# SPINE_CONNECTOR.net
KiCad netlist of a schematic drawn in Altium Designer
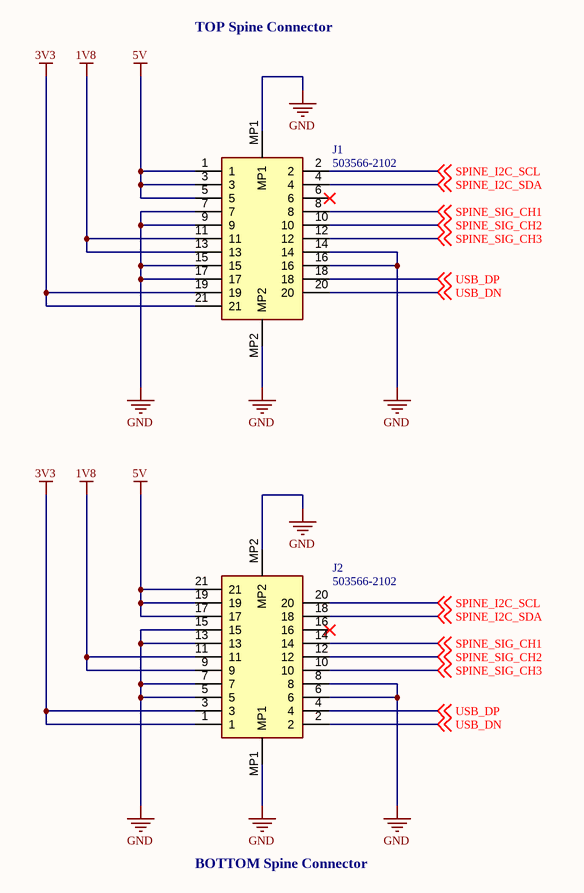
[diagram p0: SPINE_CONNECTOR.SchDoc]

(export (version "E")
  (design (tool "Eeschema 10.0.6"))
  (components
    (comp (ref "J1")
      (value "503566-2102")
      (footprint "SamacSys:5035662102")
      (description "Connector")
      (fields (field (name "MOUSER PART NUMBER") "538-503566-2102"))
      (libsource (lib "*") (part "503566-2102"))
    )
    (comp (ref "J2")
      (value "503566-2102")
      (footprint "SamacSys:5035662102")
      (description "Connector")
      (fields (field (name "MOUSER PART NUMBER") "538-503566-2102"))
      (libsource (lib "") (part "503566-2102_1"))
    )
  )
  (nets
    (net (code "1") (name "1V8") (class "Default")
      (node (ref "J1") (pin "11") (pinfunction "11_11") (pintype "passive"))
      (node (ref "J1") (pin "13") (pinfunction "13_13") (pintype "passive"))
      (node (ref "J2") (pin "11") (pinfunction "11_11") (pintype "passive"))
      (node (ref "J2") (pin "9") (pinfunction "9_9") (pintype "passive"))
    )
    (net (code "2") (name "3V3") (class "Default")
      (node (ref "J1") (pin "19") (pinfunction "19_19") (pintype "passive"))
      (node (ref "J1") (pin "21") (pinfunction "21_21") (pintype "passive"))
      (node (ref "J2") (pin "1") (pinfunction "1_1") (pintype "passive"))
      (node (ref "J2") (pin "3") (pinfunction "3_3") (pintype "passive"))
    )
    (net (code "3") (name "5V") (class "Default")
      (node (ref "J1") (pin "1") (pinfunction "1_1") (pintype "passive"))
      (node (ref "J1") (pin "3") (pinfunction "3_3") (pintype "passive"))
      (node (ref "J1") (pin "5") (pinfunction "5_5") (pintype "passive"))
      (node (ref "J2") (pin "17") (pinfunction "17_17") (pintype "passive"))
      (node (ref "J2") (pin "19") (pinfunction "19_19") (pintype "passive"))
      (node (ref "J2") (pin "21") (pinfunction "21_21") (pintype "passive"))
    )
    (net (code "4") (name "GND") (class "Default")
      (node (ref "J1") (pin "14") (pinfunction "14_14") (pintype "passive"))
      (node (ref "J1") (pin "15") (pinfunction "15_15") (pintype "passive"))
      (node (ref "J1") (pin "16") (pinfunction "16_16") (pintype "passive"))
      (node (ref "J1") (pin "17") (pinfunction "17_17") (pintype "passive"))
      (node (ref "J1") (pin "7") (pinfunction "7_7") (pintype "passive"))
      (node (ref "J1") (pin "9") (pinfunction "9_9") (pintype "passive"))
      (node (ref "J1") (pin "MP1") (pinfunction "MP1_MP1") (pintype "passive"))
      (node (ref "J1") (pin "MP2") (pinfunction "MP2_MP2") (pintype "passive"))
      (node (ref "J2") (pin "13") (pinfunction "13_13") (pintype "passive"))
      (node (ref "J2") (pin "15") (pinfunction "15_15") (pintype "passive"))
      (node (ref "J2") (pin "5") (pinfunction "5_5") (pintype "passive"))
      (node (ref "J2") (pin "6") (pinfunction "6_6") (pintype "passive"))
      (node (ref "J2") (pin "7") (pinfunction "7_7") (pintype "passive"))
      (node (ref "J2") (pin "8") (pinfunction "8_8") (pintype "passive"))
      (node (ref "J2") (pin "MP1") (pinfunction "MP1_MP1") (pintype "passive"))
      (node (ref "J2") (pin "MP2") (pinfunction "MP2_MP2") (pintype "passive"))
    )
    (net (code "5") (name "SPINE_I2C_SCL") (class "Default")
      (node (ref "J1") (pin "2") (pinfunction "2_2") (pintype "passive"))
      (node (ref "J2") (pin "20") (pinfunction "20_20") (pintype "passive"))
    )
    (net (code "6") (name "SPINE_I2C_SDA") (class "Default")
      (node (ref "J1") (pin "4") (pinfunction "4_4") (pintype "passive"))
      (node (ref "J2") (pin "18") (pinfunction "18_18") (pintype "passive"))
    )
    (net (code "7") (name "SPINE_SIG_CH1") (class "Default")
      (node (ref "J1") (pin "8") (pinfunction "8_8") (pintype "passive"))
      (node (ref "J2") (pin "14") (pinfunction "14_14") (pintype "passive"))
    )
    (net (code "8") (name "SPINE_SIG_CH2") (class "Default")
      (node (ref "J1") (pin "10") (pinfunction "10_10") (pintype "passive"))
      (node (ref "J2") (pin "12") (pinfunction "12_12") (pintype "passive"))
    )
    (net (code "9") (name "SPINE_SIG_CH3") (class "Default")
      (node (ref "J1") (pin "12") (pinfunction "12_12") (pintype "passive"))
      (node (ref "J2") (pin "10") (pinfunction "10_10") (pintype "passive"))
    )
    (net (code "10") (name "USB_DN") (class "Default")
      (node (ref "J1") (pin "20") (pinfunction "20_20") (pintype "passive"))
      (node (ref "J2") (pin "2") (pinfunction "2_2") (pintype "passive"))
    )
    (net (code "11") (name "USB_DP") (class "Default")
      (node (ref "J1") (pin "18") (pinfunction "18_18") (pintype "passive"))
      (node (ref "J2") (pin "4") (pinfunction "4_4") (pintype "passive"))
    )
    (net (code "12") (name "unconnected-(J1-Pad6)") (class "Default")
      (node (ref "J1") (pin "6") (pinfunction "6_6") (pintype "passive+no_connect"))
    )
    (net (code "13") (name "unconnected-(J2-Pad16)") (class "Default")
      (node (ref "J2") (pin "16") (pinfunction "16_16") (pintype "passive+no_connect"))
    )
  )
)
